# design.net
KiCad netlist of a schematic drawn in Altium Designer
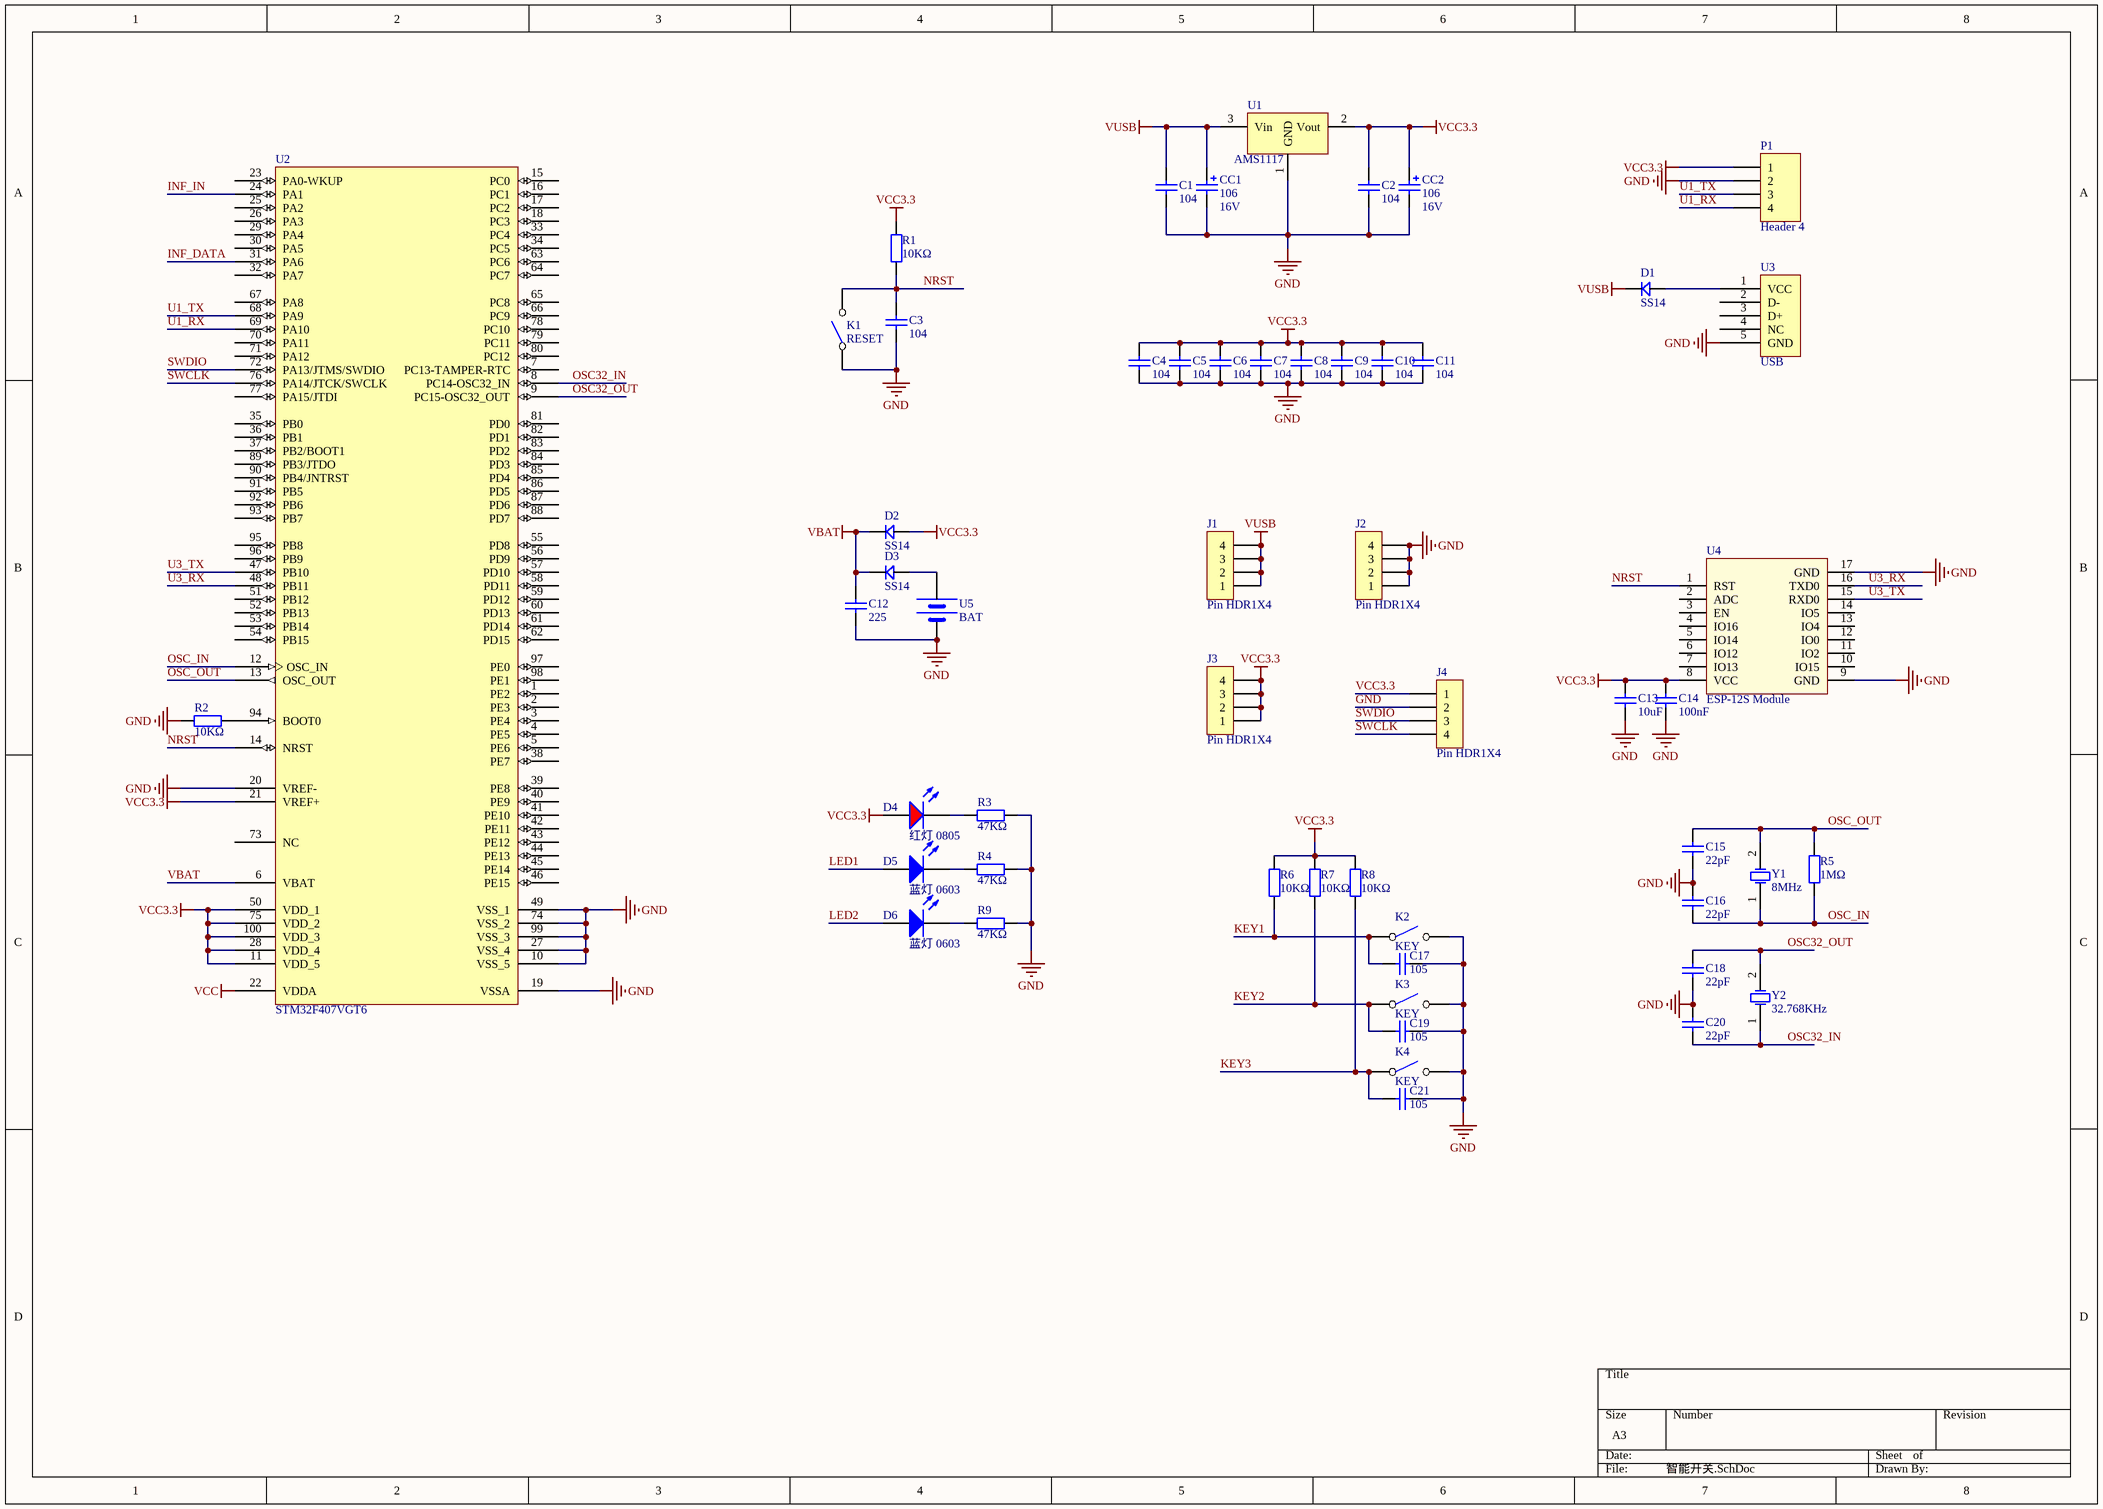
[diagram p0: 智能开关.SchDoc]

(export (version "E")
  (design (tool "Eeschema 10.0.6"))
  (components
    (comp (ref "C1")
      (value "104")
      (footprint "LC-0805_C")
      (description "贴片电容")
      (libsource (lib "Miscellaneous Devices LC") (part "0805 6.8nF (682) 10% 50V"))
    )
    (comp (ref "C2")
      (value "104")
      (footprint "LC-0805_C")
      (description "贴片电容")
      (libsource (lib "Miscellaneous Devices LC") (part "0805 6.8nF (682) 10% 50V"))
    )
    (comp (ref "C3")
      (value "104")
      (footprint "LC-0805_C")
      (description "贴片电容")
      (libsource (lib "Miscellaneous Devices LC") (part "0805 330nF (334) 10% 50V"))
    )
    (comp (ref "C4")
      (value "104")
      (footprint "LC-0805_C")
      (description "贴片电容")
      (libsource (lib "Miscellaneous Devices LC") (part "0805 6.8nF (682) 10% 50V"))
    )
    (comp (ref "C5")
      (value "104")
      (footprint "LC-0805_C")
      (description "贴片电容")
      (libsource (lib "Miscellaneous Devices LC") (part "0805 6.8nF (682) 10% 50V"))
    )
    (comp (ref "C6")
      (value "104")
      (footprint "LC-0805_C")
      (description "贴片电容")
      (libsource (lib "Miscellaneous Devices LC") (part "0805 6.8nF (682) 10% 50V"))
    )
    (comp (ref "C7")
      (value "104")
      (footprint "LC-0805_C")
      (description "贴片电容")
      (libsource (lib "Miscellaneous Devices LC") (part "0805 6.8nF (682) 10% 50V"))
    )
    (comp (ref "C8")
      (value "104")
      (footprint "LC-0805_C")
      (description "贴片电容")
      (libsource (lib "Miscellaneous Devices LC") (part "0805 6.8nF (682) 10% 50V"))
    )
    (comp (ref "C9")
      (value "104")
      (footprint "LC-0805_C")
      (description "贴片电容")
      (libsource (lib "Miscellaneous Devices LC") (part "0805 6.8nF (682) 10% 50V"))
    )
    (comp (ref "C10")
      (value "104")
      (footprint "LC-0805_C")
      (description "贴片电容")
      (libsource (lib "Miscellaneous Devices LC") (part "0805 6.8nF (682) 10% 50V"))
    )
    (comp (ref "C11")
      (value "104")
      (footprint "LC-0805_C")
      (description "贴片电容")
      (libsource (lib "Miscellaneous Devices LC") (part "0805 6.8nF (682) 10% 50V"))
    )
    (comp (ref "C12")
      (value "225")
      (footprint "LC-0805_C")
      (description "贴片电容")
      (libsource (lib "Miscellaneous Devices LC") (part "0805 6.8nF (682) 10% 50V"))
    )
    (comp (ref "C13")
      (value "10uF")
      (footprint "LC-0805_C")
      (description "贴片电容")
      (libsource (lib "Miscellaneous Devices LC") (part "0805 6.8nF (682) 10% 50V"))
    )
    (comp (ref "C14")
      (value "100nF")
      (footprint "LC-0805_C")
      (description "贴片电容")
      (libsource (lib "Miscellaneous Devices LC") (part "0805 6.8nF (682) 10% 50V"))
    )
    (comp (ref "C15")
      (value "22pF")
      (footprint "LC-0805_C")
      (description "贴片电容")
      (libsource (lib "Miscellaneous Devices LC") (part "0805 6pF (6R0) 0.25pF 50V"))
    )
    (comp (ref "C16")
      (value "22pF")
      (footprint "LC-0805_C")
      (description "贴片电容")
      (libsource (lib "Miscellaneous Devices LC") (part "0805 6pF (6R0) 0.25pF 50V"))
    )
    (comp (ref "C17")
      (value "105")
      (footprint "LC-0805_C")
      (description "贴片电容")
      (libsource (lib "Miscellaneous Devices LC") (part "0805 6.8nF (682) 10% 50V"))
    )
    (comp (ref "C18")
      (value "22pF")
      (footprint "LC-0805_C")
      (description "贴片电容")
      (libsource (lib "Miscellaneous Devices LC") (part "0805 6pF (6R0) 0.25pF 50V"))
    )
    (comp (ref "C19")
      (value "105")
      (footprint "LC-0805_C")
      (description "贴片电容")
      (libsource (lib "Miscellaneous Devices LC") (part "0805 6.8nF (682) 10% 50V"))
    )
    (comp (ref "C20")
      (value "22pF")
      (footprint "LC-0805_C")
      (description "贴片电容")
      (libsource (lib "Miscellaneous Devices LC") (part "0805 6pF (6R0) 0.25pF 50V"))
    )
    (comp (ref "C21")
      (value "105")
      (footprint "LC-0805_C")
      (description "贴片电容")
      (libsource (lib "Miscellaneous Devices LC") (part "0805 6.8nF (682) 10% 50V"))
    )
    (comp (ref "CC1")
      (value "Cap Tan C")
      (footprint "TAN-C-6032")
      (description "Polarized Capacitor (Radial)")
      (fields
        (field (name "CAPACITANCE") "106")
        (field (name "VOLTAGE") "16V")
        (field (name "PUBLISHER") "Altium Limited")
      )
      (libsource (lib "MyLib") (part "Cap Tan C"))
    )
    (comp (ref "CC2")
      (value "Cap Tan C")
      (footprint "TAN-C-6032")
      (description "Polarized Capacitor (Radial)")
      (fields
        (field (name "CAPACITANCE") "106")
        (field (name "VOLTAGE") "16V")
        (field (name "PUBLISHER") "Altium Limited")
      )
      (libsource (lib "MyLib") (part "Cap Tan C"))
    )
    (comp (ref "D1")
      (value "SS14")
      (footprint "Miscellaneous Devices LC:LC-SOD-123")
      (libsource (lib "Explorer STM32F407封装库") (part "D"))
    )
    (comp (ref "D2")
      (value "SS14")
      (footprint "Miscellaneous Devices LC:LC-SOD-123")
      (libsource (lib "Explorer STM32F407封装库") (part "D"))
    )
    (comp (ref "D3")
      (value "SS14")
      (footprint "Miscellaneous Devices LC:LC-SOD-123")
      (libsource (lib "Explorer STM32F407封装库") (part "D"))
    )
    (comp (ref "D4")
      (value "红灯 0805")
      (footprint "LC-0805_LED_S1")
      (description "发光二极管")
      (libsource (lib "Miscellaneous Devices LC") (part "0805 红灯"))
    )
    (comp (ref "D5")
      (value "蓝灯 0603")
      (footprint "Miscellaneous Devices LC:LC-0805_LED_S1")
      (description "发光二极管")
      (libsource (lib "Miscellaneous Devices LC") (part "0603 蓝灯"))
    )
    (comp (ref "D6")
      (value "蓝灯 0603")
      (footprint "Miscellaneous Devices LC:LC-0805_LED_S1")
      (description "发光二极管")
      (libsource (lib "Miscellaneous Devices LC") (part "0603 蓝灯"))
    )
    (comp (ref "J1")
      (value "Pin HDR1X4")
      (footprint "Pin HDR1X4/2.54mm-S")
      (libsource (lib "排针") (part "Pin HDR1X4"))
    )
    (comp (ref "J2")
      (value "Pin HDR1X4")
      (footprint "Pin HDR1X4/2.54mm-S")
      (libsource (lib "排针") (part "Pin HDR1X4"))
    )
    (comp (ref "J3")
      (value "Pin HDR1X4")
      (footprint "Pin HDR1X4/2.54mm-S")
      (libsource (lib "排针") (part "Pin HDR1X4"))
    )
    (comp (ref "J4")
      (value "Pin HDR1X4")
      (footprint "Pin HDR1X4/2.54mm-S")
      (libsource (lib "") (part "Pin HDR1X4_1"))
    )
    (comp (ref "K1")
      (value "RESET")
      (footprint "MyLib:KEY_2")
      (description "微动开关")
      (libsource (lib "MyLib") (part "KEY"))
    )
    (comp (ref "K2")
      (value "KEY")
      (footprint "MyLib:KEY_2")
      (description "微动开关")
      (libsource (lib "MyLib") (part "KEY"))
    )
    (comp (ref "K3")
      (value "KEY")
      (footprint "MyLib:KEY_2")
      (description "微动开关")
      (libsource (lib "MyLib") (part "KEY"))
    )
    (comp (ref "K4")
      (value "KEY")
      (footprint "MyLib:KEY_2")
      (description "微动开关")
      (libsource (lib "MyLib") (part "KEY"))
    )
    (comp (ref "P1")
      (value "Header 4")
      (footprint "MyLib:HDR1X4")
      (description "Header, 4-Pin")
      (fields (field (name "PUBLISHER") "Altium Limited"))
      (libsource (lib "MyLib") (part "Header 4"))
    )
    (comp (ref "R1")
      (value "10KΩ")
      (footprint "LC-0805_R")
      (description "贴片电阻")
      (libsource (lib "Miscellaneous Devices LC") (part "0805 390KΩ (3903) 1%"))
    )
    (comp (ref "R2")
      (value "10KΩ")
      (footprint "LC-0805_R")
      (description "贴片电阻")
      (libsource (lib "Miscellaneous Devices LC") (part "0805 1.8KΩ (1801) 1%"))
    )
    (comp (ref "R3")
      (value "47KΩ")
      (footprint "LC-0805_R")
      (description "贴片电阻")
      (libsource (lib "Miscellaneous Devices LC") (part "0805 11KΩ (1102) 1%"))
    )
    (comp (ref "R4")
      (value "47KΩ")
      (footprint "LC-0805_R")
      (description "贴片电阻")
      (libsource (lib "Miscellaneous Devices LC") (part "0805 11KΩ (1102) 1%"))
    )
    (comp (ref "R5")
      (value "1MΩ")
      (footprint "LC-0805_R")
      (description "贴片电阻")
      (libsource (lib "Miscellaneous Devices LC") (part "0805 390KΩ (3903) 1%"))
    )
    (comp (ref "R6")
      (value "10KΩ")
      (footprint "LC-0805_R")
      (description "贴片电阻")
      (libsource (lib "") (part "0805 11KΩ (1102) 1%_1"))
    )
    (comp (ref "R7")
      (value "10KΩ")
      (footprint "LC-0805_R")
      (description "贴片电阻")
      (libsource (lib "") (part "0805 11KΩ (1102) 1%_1"))
    )
    (comp (ref "R8")
      (value "10KΩ")
      (footprint "LC-0805_R")
      (description "贴片电阻")
      (libsource (lib "") (part "0805 11KΩ (1102) 1%_1"))
    )
    (comp (ref "R9")
      (value "47KΩ")
      (footprint "LC-0805_R")
      (description "贴片电阻")
      (libsource (lib "Miscellaneous Devices LC") (part "0805 11KΩ (1102) 1%"))
    )
    (comp (ref "U1")
      (value "AMS1117")
      (footprint "MyLib:SOT-223")
      (description "3.3V电压转换器AMS1117")
      (libsource (lib "My Footprint") (part "AMS1117"))
    )
    (comp (ref "U2")
      (value "STM32F407VGT6")
      (footprint "LQFP100 14x14")
      (fields (field (name "PUBLISHER") "*"))
      (libsource (lib "STM32系列") (part "STM32F103VBT6"))
    )
    (comp (ref "U3") (value "USB") (footprint "MyLib:USB_B") (libsource (lib "MyLib") (part "USB")))
    (comp (ref "U4")
      (value "ESP-12S Module")
      (footprint "ESP-12S Module")
      (libsource (lib "MyLib") (part "ESP-12S Module"))
    )
    (comp (ref "U5")
      (value "BAT")
      (footprint "MyLib:CR1220_A")
      (description "纽扣电池座CR1220")
      (libsource (lib "MyLib") (part "BAT"))
    )
    (comp (ref "Y1")
      (value "8MHz")
      (footprint "MyLib:XTAL-SMD")
      (description "晶体振荡器")
      (fields (field (name "PUBLISHER") "Altium Limited"))
      (libsource (lib "MyLib") (part "XTAL"))
    )
    (comp (ref "Y2")
      (value "32.768KHz")
      (footprint "晶振:OSC-3x8-WI-B")
      (description "晶体振荡器")
      (fields (field (name "PUBLISHER") "Altium Limited"))
      (libsource (lib "MyLib") (part "XTAL"))
    )
  )
  (nets
    (net (code "1") (name "/INF_DATA") (class "Default")
      (node (ref "U2") (pin "31") (pinfunction "PA6_31") (pintype "bidirectional"))
    )
    (net (code "2") (name "/INF_IN") (class "Default")
      (node (ref "U2") (pin "24") (pinfunction "PA1_24") (pintype "bidirectional"))
    )
    (net (code "3") (name "/KEY1") (class "Default")
      (node (ref "C17") (pin "1") (pinfunction "1_1") (pintype "passive"))
      (node (ref "K2") (pin "1") (pinfunction "1_1") (pintype "passive"))
      (node (ref "R6") (pin "1") (pinfunction "1_1") (pintype "passive"))
    )
    (net (code "4") (name "/KEY2") (class "Default")
      (node (ref "C19") (pin "1") (pinfunction "1_1") (pintype "passive"))
      (node (ref "K3") (pin "1") (pinfunction "1_1") (pintype "passive"))
      (node (ref "R7") (pin "1") (pinfunction "1_1") (pintype "passive"))
    )
    (net (code "5") (name "/KEY3") (class "Default")
      (node (ref "C21") (pin "1") (pinfunction "1_1") (pintype "passive"))
      (node (ref "K4") (pin "1") (pinfunction "1_1") (pintype "passive"))
      (node (ref "R8") (pin "1") (pinfunction "1_1") (pintype "passive"))
    )
    (net (code "6") (name "/LED1") (class "Default")
      (node (ref "D5") (pin "A") (pinfunction "A_A") (pintype "passive"))
    )
    (net (code "7") (name "/LED2") (class "Default")
      (node (ref "D6") (pin "A") (pinfunction "A_A") (pintype "passive"))
    )
    (net (code "8") (name "/NRST") (class "Default")
      (node (ref "C3") (pin "2") (pinfunction "2_2") (pintype "passive"))
      (node (ref "K1") (pin "2") (pinfunction "2_2") (pintype "passive"))
      (node (ref "R1") (pin "1") (pinfunction "1_1") (pintype "passive"))
      (node (ref "U2") (pin "14") (pinfunction "NRST_14") (pintype "bidirectional"))
      (node (ref "U4") (pin "1") (pinfunction "RST_1") (pintype "passive"))
    )
    (net (code "9") (name "/OSC32_IN") (class "Default")
      (node (ref "C20") (pin "1") (pinfunction "1_1") (pintype "passive"))
      (node (ref "U2") (pin "8") (pinfunction "PC14-OSC32_IN_8") (pintype "bidirectional"))
      (node (ref "Y2") (pin "1") (pinfunction "OSC1_1") (pintype "passive"))
    )
    (net (code "10") (name "/OSC32_OUT") (class "Default")
      (node (ref "C18") (pin "2") (pinfunction "2_2") (pintype "passive"))
      (node (ref "U2") (pin "9") (pinfunction "PC15-OSC32_OUT_9") (pintype "bidirectional"))
      (node (ref "Y2") (pin "2") (pinfunction "OSC2_2") (pintype "passive"))
    )
    (net (code "11") (name "/OSC_IN") (class "Default")
      (node (ref "C16") (pin "1") (pinfunction "1_1") (pintype "passive"))
      (node (ref "R5") (pin "1") (pinfunction "1_1") (pintype "passive"))
      (node (ref "U2") (pin "12") (pinfunction "OSC_IN_12") (pintype "input"))
      (node (ref "Y1") (pin "1") (pinfunction "OSC1_1") (pintype "passive"))
    )
    (net (code "12") (name "/OSC_OUT") (class "Default")
      (node (ref "C15") (pin "2") (pinfunction "2_2") (pintype "passive"))
      (node (ref "R5") (pin "2") (pinfunction "2_2") (pintype "passive"))
      (node (ref "U2") (pin "13") (pinfunction "OSC_OUT_13") (pintype "output"))
      (node (ref "Y1") (pin "2") (pinfunction "OSC2_2") (pintype "passive"))
    )
    (net (code "13") (name "/SWCLK") (class "Default")
      (node (ref "J4") (pin "4") (pinfunction "4_4") (pintype "passive"))
      (node (ref "U2") (pin "76") (pinfunction "PA14/JTCK/SWCLK_76") (pintype "bidirectional"))
    )
    (net (code "14") (name "/SWDIO") (class "Default")
      (node (ref "J4") (pin "3") (pinfunction "3_3") (pintype "passive"))
      (node (ref "U2") (pin "72") (pinfunction "PA13/JTMS/SWDIO_72") (pintype "bidirectional"))
    )
    (net (code "15") (name "/U1_RX") (class "Default")
      (node (ref "P1") (pin "4") (pinfunction "4_4") (pintype "passive"))
      (node (ref "U2") (pin "69") (pinfunction "PA10_69") (pintype "bidirectional"))
    )
    (net (code "16") (name "/U1_TX") (class "Default")
      (node (ref "P1") (pin "3") (pinfunction "3_3") (pintype "passive"))
      (node (ref "U2") (pin "68") (pinfunction "PA9_68") (pintype "bidirectional"))
    )
    (net (code "17") (name "/U3_RX") (class "Default")
      (node (ref "U2") (pin "48") (pinfunction "PB11_48") (pintype "bidirectional"))
      (node (ref "U4") (pin "16") (pinfunction "TXD0_16") (pintype "passive"))
    )
    (net (code "18") (name "/U3_TX") (class "Default")
      (node (ref "U2") (pin "47") (pinfunction "PB10_47") (pintype "bidirectional"))
      (node (ref "U4") (pin "15") (pinfunction "RXD0_15") (pintype "passive"))
    )
    (net (code "19") (name "GND") (class "Default")
      (node (ref "C1") (pin "1") (pinfunction "1_1") (pintype "passive"))
      (node (ref "C10") (pin "1") (pinfunction "1_1") (pintype "passive"))
      (node (ref "C11") (pin "1") (pinfunction "1_1") (pintype "passive"))
      (node (ref "C12") (pin "1") (pinfunction "1_1") (pintype "passive"))
      (node (ref "C13") (pin "1") (pinfunction "1_1") (pintype "passive"))
      (node (ref "C14") (pin "1") (pinfunction "1_1") (pintype "passive"))
      (node (ref "C15") (pin "1") (pinfunction "1_1") (pintype "passive"))
      (node (ref "C16") (pin "2") (pinfunction "2_2") (pintype "passive"))
      (node (ref "C17") (pin "2") (pinfunction "2_2") (pintype "passive"))
      (node (ref "C18") (pin "1") (pinfunction "1_1") (pintype "passive"))
      (node (ref "C19") (pin "2") (pinfunction "2_2") (pintype "passive"))
      (node (ref "C2") (pin "1") (pinfunction "1_1") (pintype "passive"))
      (node (ref "C20") (pin "2") (pinfunction "2_2") (pintype "passive"))
      (node (ref "C21") (pin "2") (pinfunction "2_2") (pintype "passive"))
      (node (ref "C3") (pin "1") (pinfunction "1_1") (pintype "passive"))
      (node (ref "C4") (pin "1") (pinfunction "1_1") (pintype "passive"))
      (node (ref "C5") (pin "1") (pinfunction "1_1") (pintype "passive"))
      (node (ref "C6") (pin "1") (pinfunction "1_1") (pintype "passive"))
      (node (ref "C7") (pin "1") (pinfunction "1_1") (pintype "passive"))
      (node (ref "C8") (pin "1") (pinfunction "1_1") (pintype "passive"))
      (node (ref "C9") (pin "1") (pinfunction "1_1") (pintype "passive"))
      (node (ref "CC1") (pin "1") (pinfunction "2_1") (pintype "passive"))
      (node (ref "CC2") (pin "1") (pinfunction "2_1") (pintype "passive"))
      (node (ref "J2") (pin "1") (pinfunction "1_1") (pintype "passive"))
      (node (ref "J2") (pin "2") (pinfunction "2_2") (pintype "passive"))
      (node (ref "J2") (pin "3") (pinfunction "3_3") (pintype "passive"))
      (node (ref "J2") (pin "4") (pinfunction "4_4") (pintype "passive"))
      (node (ref "J4") (pin "2") (pinfunction "2_2") (pintype "passive"))
      (node (ref "K1") (pin "1") (pinfunction "1_1") (pintype "passive"))
      (node (ref "K2") (pin "2") (pinfunction "2_2") (pintype "passive"))
      (node (ref "K3") (pin "2") (pinfunction "2_2") (pintype "passive"))
      (node (ref "K4") (pin "2") (pinfunction "2_2") (pintype "passive"))
      (node (ref "P1") (pin "2") (pinfunction "2_2") (pintype "passive"))
      (node (ref "R2") (pin "1") (pinfunction "1_1") (pintype "passive"))
      (node (ref "R3") (pin "2") (pinfunction "2_2") (pintype "passive"))
      (node (ref "R4") (pin "2") (pinfunction "2_2") (pintype "passive"))
      (node (ref "R9") (pin "2") (pinfunction "2_2") (pintype "passive"))
      (node (ref "U1") (pin "1") (pinfunction "GND_1") (pintype "passive"))
      (node (ref "U2") (pin "10") (pinfunction "VSS_5_10") (pintype "power_in"))
      (node (ref "U2") (pin "19") (pinfunction "VSSA_19") (pintype "power_in"))
      (node (ref "U2") (pin "20") (pinfunction "VREF-_20") (pintype "power_in"))
      (node (ref "U2") (pin "27") (pinfunction "VSS_4_27") (pintype "power_in"))
      (node (ref "U2") (pin "49") (pinfunction "VSS_1_49") (pintype "power_in"))
      (node (ref "U2") (pin "74") (pinfunction "VSS_2_74") (pintype "power_in"))
      (node (ref "U2") (pin "99") (pinfunction "VSS_3_99") (pintype "power_in"))
      (node (ref "U3") (pin "5") (pinfunction "GND_5") (pintype "passive"))
      (node (ref "U4") (pin "17") (pinfunction "GND_17") (pintype "passive"))
      (node (ref "U4") (pin "9") (pinfunction "GND_9") (pintype "passive"))
      (node (ref "U5") (pin "2") (pinfunction "GND_2") (pintype "passive"))
    )
    (net (code "20") (name "Net-(D4-PadK)") (class "Default")
      (node (ref "D4") (pin "K") (pinfunction "K_K") (pintype "passive"))
      (node (ref "R3") (pin "1") (pinfunction "1_1") (pintype "passive"))
    )
    (net (code "21") (name "Net-(D5-PadK)") (class "Default")
      (node (ref "D5") (pin "K") (pinfunction "K_K") (pintype "passive"))
      (node (ref "R4") (pin "1") (pinfunction "1_1") (pintype "passive"))
    )
    (net (code "22") (name "Net-(D6-PadK)") (class "Default")
      (node (ref "D6") (pin "K") (pinfunction "K_K") (pintype "passive"))
      (node (ref "R9") (pin "1") (pinfunction "1_1") (pintype "passive"))
    )
    (net (code "23") (name "Net-(U2-BOOT0)") (class "Default")
      (node (ref "R2") (pin "2") (pinfunction "2_2") (pintype "passive"))
      (node (ref "U2") (pin "94") (pinfunction "BOOT0_94") (pintype "input"))
    )
    (net (code "24") (name "Net-(U3-VCC)") (class "Default")
      (node (ref "D1") (pin "1") (pintype "passive"))
      (node (ref "U3") (pin "1") (pinfunction "VCC_1") (pintype "passive"))
    )
    (net (code "25") (name "Net-(U5-VCC)") (class "Default")
      (node (ref "D3") (pin "1") (pintype "passive"))
      (node (ref "U5") (pin "1") (pinfunction "VCC_1") (pintype "passive"))
    )
    (net (code "26") (name "VBAT") (class "Default")
      (node (ref "C12") (pin "2") (pinfunction "2_2") (pintype "passive"))
      (node (ref "D2") (pin "2") (pintype "passive"))
      (node (ref "D3") (pin "2") (pintype "passive"))
      (node (ref "U2") (pin "6") (pinfunction "VBAT_6") (pintype "power_in"))
    )
    (net (code "27") (name "VCC") (class "Default")
      (node (ref "U2") (pin "22") (pinfunction "VDDA_22") (pintype "power_in"))
    )
    (net (code "28") (name "VCC3.3") (class "Default")
      (node (ref "C10") (pin "2") (pinfunction "2_2") (pintype "passive"))
      (node (ref "C11") (pin "2") (pinfunction "2_2") (pintype "passive"))
      (node (ref "C13") (pin "2") (pinfunction "2_2") (pintype "passive"))
      (node (ref "C14") (pin "2") (pinfunction "2_2") (pintype "passive"))
      (node (ref "C2") (pin "2") (pinfunction "2_2") (pintype "passive"))
      (node (ref "C4") (pin "2") (pinfunction "2_2") (pintype "passive"))
      (node (ref "C5") (pin "2") (pinfunction "2_2") (pintype "passive"))
      (node (ref "C6") (pin "2") (pinfunction "2_2") (pintype "passive"))
      (node (ref "C7") (pin "2") (pinfunction "2_2") (pintype "passive"))
      (node (ref "C8") (pin "2") (pinfunction "2_2") (pintype "passive"))
      (node (ref "C9") (pin "2") (pinfunction "2_2") (pintype "passive"))
      (node (ref "CC2") (pin "2") (pinfunction "1_2") (pintype "passive"))
      (node (ref "D2") (pin "1") (pintype "passive"))
      (node (ref "D4") (pin "A") (pinfunction "A_A") (pintype "passive"))
      (node (ref "J3") (pin "1") (pinfunction "1_1") (pintype "passive"))
      (node (ref "J3") (pin "2") (pinfunction "2_2") (pintype "passive"))
      (node (ref "J3") (pin "3") (pinfunction "3_3") (pintype "passive"))
      (node (ref "J3") (pin "4") (pinfunction "4_4") (pintype "passive"))
      (node (ref "J4") (pin "1") (pinfunction "1_1") (pintype "passive"))
      (node (ref "P1") (pin "1") (pinfunction "1_1") (pintype "passive"))
      (node (ref "R1") (pin "2") (pinfunction "2_2") (pintype "passive"))
      (node (ref "R6") (pin "2") (pinfunction "2_2") (pintype "passive"))
      (node (ref "R7") (pin "2") (pinfunction "2_2") (pintype "passive"))
      (node (ref "R8") (pin "2") (pinfunction "2_2") (pintype "passive"))
      (node (ref "U1") (pin "2") (pinfunction "Vout_2") (pintype "passive"))
      (node (ref "U2") (pin "100") (pinfunction "VDD_3_100") (pintype "power_in"))
      (node (ref "U2") (pin "11") (pinfunction "VDD_5_11") (pintype "power_in"))
      (node (ref "U2") (pin "21") (pinfunction "VREF+_21") (pintype "power_in"))
      (node (ref "U2") (pin "28") (pinfunction "VDD_4_28") (pintype "power_in"))
      (node (ref "U2") (pin "50") (pinfunction "VDD_1_50") (pintype "power_in"))
      (node (ref "U2") (pin "75") (pinfunction "VDD_2_75") (pintype "power_in"))
      (node (ref "U4") (pin "8") (pinfunction "VCC_8") (pintype "passive"))
    )
    (net (code "29") (name "VUSB") (class "Default")
      (node (ref "C1") (pin "2") (pinfunction "2_2") (pintype "passive"))
      (node (ref "CC1") (pin "2") (pinfunction "1_2") (pintype "passive"))
      (node (ref "D1") (pin "2") (pintype "passive"))
      (node (ref "J1") (pin "1") (pinfunction "1_1") (pintype "passive"))
      (node (ref "J1") (pin "2") (pinfunction "2_2") (pintype "passive"))
      (node (ref "J1") (pin "3") (pinfunction "3_3") (pintype "passive"))
      (node (ref "J1") (pin "4") (pinfunction "4_4") (pintype "passive"))
      (node (ref "U1") (pin "3") (pinfunction "Vin_3") (pintype "passive"))
    )
    (net (code "30") (name "unconnected-(U2-NC-Pad73)") (class "Default")
      (node (ref "U2") (pin "73") (pinfunction "NC_73") (pintype "passive"))
    )
    (net (code "31") (name "unconnected-(U2-PA0-WKUP-Pad23)") (class "Default")
      (node (ref "U2") (pin "23") (pinfunction "PA0-WKUP_23") (pintype "bidirectional"))
    )
    (net (code "32") (name "unconnected-(U2-PA2-Pad25)") (class "Default")
      (node (ref "U2") (pin "25") (pinfunction "PA2_25") (pintype "bidirectional"))
    )
    (net (code "33") (name "unconnected-(U2-PA3-Pad26)") (class "Default")
      (node (ref "U2") (pin "26") (pinfunction "PA3_26") (pintype "bidirectional"))
    )
    (net (code "34") (name "unconnected-(U2-PA4-Pad29)") (class "Default")
      (node (ref "U2") (pin "29") (pinfunction "PA4_29") (pintype "bidirectional"))
    )
    (net (code "35") (name "unconnected-(U2-PA5-Pad30)") (class "Default")
      (node (ref "U2") (pin "30") (pinfunction "PA5_30") (pintype "bidirectional"))
    )
    (net (code "36") (name "unconnected-(U2-PA7-Pad32)") (class "Default")
      (node (ref "U2") (pin "32") (pinfunction "PA7_32") (pintype "bidirectional"))
    )
    (net (code "37") (name "unconnected-(U2-PA8-Pad67)") (class "Default")
      (node (ref "U2") (pin "67") (pinfunction "PA8_67") (pintype "bidirectional"))
    )
    (net (code "38") (name "unconnected-(U2-PA11-Pad70)") (class "Default")
      (node (ref "U2") (pin "70") (pinfunction "PA11_70") (pintype "bidirectional"))
    )
    (net (code "39") (name "unconnected-(U2-PA12-Pad71)") (class "Default")
      (node (ref "U2") (pin "71") (pinfunction "PA12_71") (pintype "bidirectional"))
    )
    (net (code "40") (name "unconnected-(U2-PA15{slash}JTDI-Pad77)") (class "Default")
      (node (ref "U2") (pin "77") (pinfunction "PA15/JTDI_77") (pintype "bidirectional"))
    )
    (net (code "41") (name "unconnected-(U2-PB0-Pad35)") (class "Default")
      (node (ref "U2") (pin "35") (pinfunction "PB0_35") (pintype "bidirectional"))
    )
    (net (code "42") (name "unconnected-(U2-PB1-Pad36)") (class "Default")
      (node (ref "U2") (pin "36") (pinfunction "PB1_36") (pintype "bidirectional"))
    )
    (net (code "43") (name "unconnected-(U2-PB2{slash}BOOT1-Pad37)") (class "Default")
      (node (ref "U2") (pin "37") (pinfunction "PB2/BOOT1_37") (pintype "bidirectional"))
    )
    (net (code "44") (name "unconnected-(U2-PB3{slash}JTDO-Pad89)") (class "Default")
      (node (ref "U2") (pin "89") (pinfunction "PB3/JTDO_89") (pintype "bidirectional"))
    )
    (net (code "45") (name "unconnected-(U2-PB4{slash}JNTRST-Pad90)") (class "Default")
      (node (ref "U2") (pin "90") (pinfunction "PB4/JNTRST_90") (pintype "bidirectional"))
    )
    (net (code "46") (name "unconnected-(U2-PB5-Pad91)") (class "Default")
      (node (ref "U2") (pin "91") (pinfunction "PB5_91") (pintype "bidirectional"))
    )
    (net (code "47") (name "unconnected-(U2-PB6-Pad92)") (class "Default")
      (node (ref "U2") (pin "92") (pinfunction "PB6_92") (pintype "bidirectional"))
    )
    (net (code "48") (name "unconnected-(U2-PB7-Pad93)") (class "Default")
      (node (ref "U2") (pin "93") (pinfunction "PB7_93") (pintype "bidirectional"))
    )
    (net (code "49") (name "unconnected-(U2-PB8-Pad95)") (class "Default")
      (node (ref "U2") (pin "95") (pinfunction "PB8_95") (pintype "bidirectional"))
    )
    (net (code "50") (name "unconnected-(U2-PB9-Pad96)") (class "Default")
      (node (ref "U2") (pin "96") (pinfunction "PB9_96") (pintype "bidirectional"))
    )
    (net (code "51") (name "unconnected-(U2-PB12-Pad51)") (class "Default")
      (node (ref "U2") (pin "51") (pinfunction "PB12_51") (pintype "bidirectional"))
    )
    (net (code "52") (name "unconnected-(U2-PB13-Pad52)") (class "Default")
      (node (ref "U2") (pin "52") (pinfunction "PB13_52") (pintype "bidirectional"))
    )
    (net (code "53") (name "unconnected-(U2-PB14-Pad53)") (class "Default")
      (node (ref "U2") (pin "53") (pinfunction "PB14_53") (pintype "bidirectional"))
    )
    (net (code "54") (name "unconnected-(U2-PB15-Pad54)") (class "Default")
      (node (ref "U2") (pin "54") (pinfunction "PB15_54") (pintype "bidirectional"))
    )
    (net (code "55") (name "unconnected-(U2-PC0-Pad15)") (class "Default")
      (node (ref "U2") (pin "15") (pinfunction "PC0_15") (pintype "bidirectional"))
    )
    (net (code "56") (name "unconnected-(U2-PC1-Pad16)") (class "Default")
      (node (ref "U2") (pin "16") (pinfunction "PC1_16") (pintype "bidirectional"))
    )
    (net (code "57") (name "unconnected-(U2-PC2-Pad17)") (class "Default")
      (node (ref "U2") (pin "17") (pinfunction "PC2_17") (pintype "bidirectional"))
    )
    (net (code "58") (name "unconnected-(U2-PC3-Pad18)") (class "Default")
      (node (ref "U2") (pin "18") (pinfunction "PC3_18") (pintype "bidirectional"))
    )
    (net (code "59") (name "unconnected-(U2-PC4-Pad33)") (class "Default")
      (node (ref "U2") (pin "33") (pinfunction "PC4_33") (pintype "bidirectional"))
    )
    (net (code "60") (name "unconnected-(U2-PC5-Pad34)") (class "Default")
      (node (ref "U2") (pin "34") (pinfunction "PC5_34") (pintype "bidirectional"))
    )
    (net (code "61") (name "unconnected-(U2-PC6-Pad63)") (class "Default")
      (node (ref "U2") (pin "63") (pinfunction "PC6_63") (pintype "bidirectional"))
    )
    (net (code "62") (name "unconnected-(U2-PC7-Pad64)") (class "Default")
      (node (ref "U2") (pin "64") (pinfunction "PC7_64") (pintype "bidirectional"))
    )
    (net (code "63") (name "unconnected-(U2-PC8-Pad65)") (class "Default")
      (node (ref "U2") (pin "65") (pinfunction "PC8_65") (pintype "bidirectional"))
    )
    (net (code "64") (name "unconnected-(U2-PC9-Pad66)") (class "Default")
      (node (ref "U2") (pin "66") (pinfunction "PC9_66") (pintype "bidirectional"))
    )
    (net (code "65") (name "unconnected-(U2-PC10-Pad78)") (class "Default")
      (node (ref "U2") (pin "78") (pinfunction "PC10_78") (pintype "bidirectional"))
    )
    (net (code "66") (name "unconnected-(U2-PC11-Pad79)") (class "Default")
      (node (ref "U2") (pin "79") (pinfunction "PC11_79") (pintype "bidirectional"))
    )
    (net (code "67") (name "unconnected-(U2-PC12-Pad80)") (class "Default")
      (node (ref "U2") (pin "80") (pinfunction "PC12_80") (pintype "bidirectional"))
    )
    (net (code "68") (name "unconnected-(U2-PC13-TAMPER-RTC-Pad7)") (class "Default")
      (node (ref "U2") (pin "7") (pinfunction "PC13-TAMPER-RTC_7") (pintype "bidirectional"))
    )
    (net (code "69") (name "unconnected-(U2-PD0-Pad81)") (class "Default")
      (node (ref "U2") (pin "81") (pinfunction "PD0_81") (pintype "bidirectional"))
    )
    (net (code "70") (name "unconnected-(U2-PD1-Pad82)") (class "Default")
      (node (ref "U2") (pin "82") (pinfunction "PD1_82") (pintype "bidirectional"))
    )
    (net (code "71") (name "unconnected-(U2-PD2-Pad83)") (class "Default")
      (node (ref "U2") (pin "83") (pinfunction "PD2_83") (pintype "bidirectional"))
    )
    (net (code "72") (name "unconnected-(U2-PD3-Pad84)") (class "Default")
      (node (ref "U2") (pin "84") (pinfunction "PD3_84") (pintype "bidirectional"))
    )
    (net (code "73") (name "unconnected-(U2-PD4-Pad85)") (class "Default")
      (node (ref "U2") (pin "85") (pinfunction "PD4_85") (pintype "bidirectional"))
    )
    (net (code "74") (name "unconnected-(U2-PD5-Pad86)") (class "Default")
      (node (ref "U2") (pin "86") (pinfunction "PD5_86") (pintype "bidirectional"))
    )
    (net (code "75") (name "unconnected-(U2-PD6-Pad87)") (class "Default")
      (node (ref "U2") (pin "87") (pinfunction "PD6_87") (pintype "bidirectional"))
    )
    (net (code "76") (name "unconnected-(U2-PD7-Pad88)") (class "Default")
      (node (ref "U2") (pin "88") (pinfunction "PD7_88") (pintype "bidirectional"))
    )
    (net (code "77") (name "unconnected-(U2-PD8-Pad55)") (class "Default")
      (node (ref "U2") (pin "55") (pinfunction "PD8_55") (pintype "bidirectional"))
    )
    (net (code "78") (name "unconnected-(U2-PD9-Pad56)") (class "Default")
      (node (ref "U2") (pin "56") (pinfunction "PD9_56") (pintype "bidirectional"))
    )
    (net (code "79") (name "unconnected-(U2-PD10-Pad57)") (class "Default")
      (node (ref "U2") (pin "57") (pinfunction "PD10_57") (pintype "bidirectional"))
    )
    (net (code "80") (name "unconnected-(U2-PD11-Pad58)") (class "Default")
      (node (ref "U2") (pin "58") (pinfunction "PD11_58") (pintype "bidirectional"))
    )
    (net (code "81") (name "unconnected-(U2-PD12-Pad59)") (class "Default")
      (node (ref "U2") (pin "59") (pinfunction "PD12_59") (pintype "bidirectional"))
    )
    (net (code "82") (name "unconnected-(U2-PD13-Pad60)") (class "Default")
      (node (ref "U2") (pin "60") (pinfunction "PD13_60") (pintype "bidirectional"))
    )
    (net (code "83") (name "unconnected-(U2-PD14-Pad61)") (class "Default")
      (node (ref "U2") (pin "61") (pinfunction "PD14_61") (pintype "bidirectional"))
    )
    (net (code "84") (name "unconnected-(U2-PD15-Pad62)") (class "Default")
      (node (ref "U2") (pin "62") (pinfunction "PD15_62") (pintype "bidirectional"))
    )
    (net (code "85") (name "unconnected-(U2-PE0-Pad97)") (class "Default")
      (node (ref "U2") (pin "97") (pinfunction "PE0_97") (pintype "bidirectional"))
    )
    (net (code "86") (name "unconnected-(U2-PE1-Pad98)") (class "Default")
      (node (ref "U2") (pin "98") (pinfunction "PE1_98") (pintype "bidirectional"))
    )
    (net (code "87") (name "unconnected-(U2-PE2-Pad1)") (class "Default")
      (node (ref "U2") (pin "1") (pinfunction "PE2_1") (pintype "bidirectional"))
    )
    (net (code "88") (name "unconnected-(U2-PE3-Pad2)") (class "Default")
      (node (ref "U2") (pin "2") (pinfunction "PE3_2") (pintype "bidirectional"))
    )
    (net (code "89") (name "unconnected-(U2-PE4-Pad3)") (class "Default")
      (node (ref "U2") (pin "3") (pinfunction "PE4_3") (pintype "bidirectional"))
    )
    (net (code "90") (name "unconnected-(U2-PE5-Pad4)") (class "Default")
      (node (ref "U2") (pin "4") (pinfunction "PE5_4") (pintype "bidirectional"))
    )
    (net (code "91") (name "unconnected-(U2-PE6-Pad5)") (class "Default")
      (node (ref "U2") (pin "5") (pinfunction "PE6_5") (pintype "bidirectional"))
    )
    (net (code "92") (name "unconnected-(U2-PE7-Pad38)") (class "Default")
      (node (ref "U2") (pin "38") (pinfunction "PE7_38") (pintype "bidirectional"))
    )
    (net (code "93") (name "unconnected-(U2-PE8-Pad39)") (class "Default")
      (node (ref "U2") (pin "39") (pinfunction "PE8_39") (pintype "bidirectional"))
    )
    (net (code "94") (name "unconnected-(U2-PE9-Pad40)") (class "Default")
      (node (ref "U2") (pin "40") (pinfunction "PE9_40") (pintype "bidirectional"))
    )
    (net (code "95") (name "unconnected-(U2-PE10-Pad41)") (class "Default")
      (node (ref "U2") (pin "41") (pinfunction "PE10_41") (pintype "bidirectional"))
    )
    (net (code "96") (name "unconnected-(U2-PE11-Pad42)") (class "Default")
      (node (ref "U2") (pin "42") (pinfunction "PE11_42") (pintype "bidirectional"))
    )
    (net (code "97") (name "unconnected-(U2-PE12-Pad43)") (class "Default")
      (node (ref "U2") (pin "43") (pinfunction "PE12_43") (pintype "bidirectional"))
    )
    (net (code "98") (name "unconnected-(U2-PE13-Pad44)") (class "Default")
      (node (ref "U2") (pin "44") (pinfunction "PE13_44") (pintype "bidirectional"))
    )
    (net (code "99") (name "unconnected-(U2-PE14-Pad45)") (class "Default")
      (node (ref "U2") (pin "45") (pinfunction "PE14_45") (pintype "bidirectional"))
    )
    (net (code "100") (name "unconnected-(U2-PE15-Pad46)") (class "Default")
      (node (ref "U2") (pin "46") (pinfunction "PE15_46") (pintype "bidirectional"))
    )
    (net (code "101") (name "unconnected-(U3-D+-Pad3)") (class "Default")
      (node (ref "U3") (pin "3") (pinfunction "D+_3") (pintype "passive"))
    )
    (net (code "102") (name "unconnected-(U3-D--Pad2)") (class "Default")
      (node (ref "U3") (pin "2") (pinfunction "D-_2") (pintype "passive"))
    )
    (net (code "103") (name "unconnected-(U3-NC-Pad4)") (class "Default")
      (node (ref "U3") (pin "4") (pinfunction "NC_4") (pintype "passive"))
    )
    (net (code "104") (name "unconnected-(U4-ADC-Pad2)") (class "Default")
      (node (ref "U4") (pin "2") (pinfunction "ADC_2") (pintype "passive"))
    )
    (net (code "105") (name "unconnected-(U4-EN-Pad3)") (class "Default")
      (node (ref "U4") (pin "3") (pinfunction "EN_3") (pintype "passive"))
    )
    (net (code "106") (name "unconnected-(U4-IO0-Pad12)") (class "Default")
      (node (ref "U4") (pin "12") (pinfunction "IO0_12") (pintype "passive"))
    )
    (net (code "107") (name "unconnected-(U4-IO2-Pad11)") (class "Default")
      (node (ref "U4") (pin "11") (pinfunction "IO2_11") (pintype "passive"))
    )
    (net (code "108") (name "unconnected-(U4-IO4-Pad13)") (class "Default")
      (node (ref "U4") (pin "13") (pinfunction "IO4_13") (pintype "passive"))
    )
    (net (code "109") (name "unconnected-(U4-IO5-Pad14)") (class "Default")
      (node (ref "U4") (pin "14") (pinfunction "IO5_14") (pintype "passive"))
    )
    (net (code "110") (name "unconnected-(U4-IO12-Pad6)") (class "Default")
      (node (ref "U4") (pin "6") (pinfunction "IO12_6") (pintype "passive"))
    )
    (net (code "111") (name "unconnected-(U4-IO13-Pad7)") (class "Default")
      (node (ref "U4") (pin "7") (pinfunction "IO13_7") (pintype "passive"))
    )
    (net (code "112") (name "unconnected-(U4-IO14-Pad5)") (class "Default")
      (node (ref "U4") (pin "5") (pinfunction "IO14_5") (pintype "passive"))
    )
    (net (code "113") (name "unconnected-(U4-IO15-Pad10)") (class "Default")
      (node (ref "U4") (pin "10") (pinfunction "IO15_10") (pintype "passive"))
    )
    (net (code "114") (name "unconnected-(U4-IO16-Pad4)") (class "Default")
      (node (ref "U4") (pin "4") (pinfunction "IO16_4") (pintype "passive"))
    )
  )
)
